# Intelligent_Agriculture_Power.net
KiCad netlist of a schematic drawn in Altium Designer
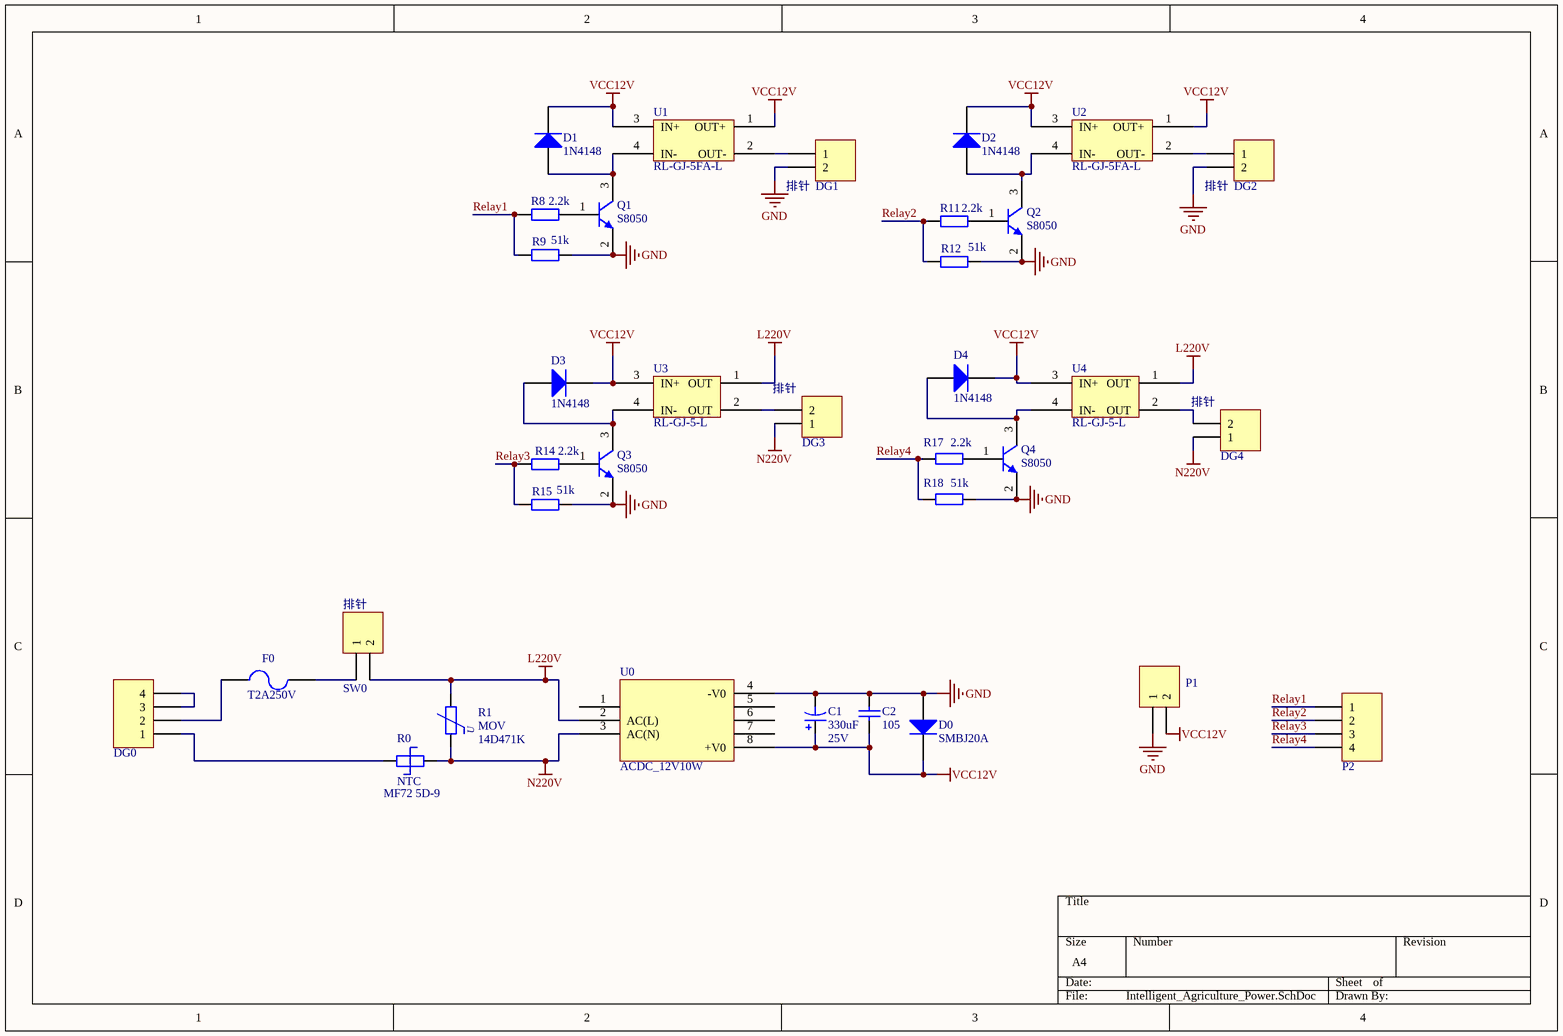
[diagram p0: Intelligent_Agriculture_Power.SchDoc]

(export (version "E")
  (design (tool "Eeschema 10.0.6"))
  (components
    (comp (ref "C1")
      (value "330uF")
      (footprint "C-RB-2.54")
      (description "电解电容")
      (fields
        (field (name "VOL") "25V")
        (field (name "Comment") "Cap Pol1")
        (field (name "PUBLISHER") "Altium Limited")
      )
      (libsource (lib "Miscellaneous Devices") (part "Cap Pol1"))
    )
    (comp (ref "C2")
      (value "105")
      (footprint "C-RAD-0805")
      (description "无极性电容")
      (fields (field (name "Comment") "Cap") (field (name "PUBLISHER") "Altium Limited"))
      (libsource (lib "Intelligent_Agriculture_Lib") (part "Cap"))
    )
    (comp (ref "D0")
      (value "SMBJ20A")
      (footprint "DIODE-1206")
      (description "二极管")
      (fields (field (name "Comment") "Diode") (field (name "PUBLISHER") "Altium Limited"))
      (libsource (lib "Intelligent_Agriculture_Lib") (part "Diode"))
    )
    (comp (ref "D1")
      (value "1N4148")
      (footprint "DIODE-1206")
      (description "二极管")
      (fields (field (name "Comment") "Diode") (field (name "PUBLISHER") "Altium Limited"))
      (libsource (lib "Intelligent_Agriculture_Lib") (part "Diode"))
    )
    (comp (ref "D2")
      (value "1N4148")
      (footprint "DIODE-1206")
      (description "二极管")
      (fields (field (name "Comment") "Diode") (field (name "PUBLISHER") "Altium Limited"))
      (libsource (lib "Intelligent_Agriculture_Lib") (part "Diode"))
    )
    (comp (ref "D3")
      (value "1N4148")
      (footprint "DIODE-1206")
      (description "二极管")
      (fields (field (name "Comment") "Diode") (field (name "PUBLISHER") "Altium Limited"))
      (libsource (lib "Intelligent_Agriculture_Lib") (part "Diode"))
    )
    (comp (ref "D4")
      (value "1N4148")
      (footprint "DIODE-1206")
      (description "二极管")
      (fields (field (name "Comment") "Diode") (field (name "PUBLISHER") "Altium Limited"))
      (libsource (lib "Intelligent_Agriculture_Lib") (part "Diode"))
    )
    (comp (ref "DG0")
      (value "Header 4")
      (footprint "DG301-4P")
      (description "接插件")
      (fields (field (name "PUBLISHER") "Altium Limited"))
      (libsource (lib "Intelligent_Agriculture_Lib") (part "Header 4"))
    )
    (comp (ref "DG1")
      (value "Header 2")
      (footprint "DG301-2P")
      (description "接插件")
      (fields (field (name "PUBLISHER") "Altium Limited"))
      (libsource (lib "Intelligent_Agriculture_Lib") (part "Header 2"))
    )
    (comp (ref "DG2")
      (value "Header 2")
      (footprint "DG301-2P")
      (description "接插件")
      (fields (field (name "PUBLISHER") "Altium Limited"))
      (libsource (lib "Intelligent_Agriculture_Lib") (part "Header 2"))
    )
    (comp (ref "DG3")
      (value "Header 2")
      (footprint "DG301-2P")
      (description "接插件")
      (fields (field (name "PUBLISHER") "Altium Limited"))
      (libsource (lib "") (part "Header 2_1"))
    )
    (comp (ref "DG4")
      (value "Header 2")
      (footprint "DG301-2P")
      (description "接插件")
      (fields (field (name "PUBLISHER") "Altium Limited"))
      (libsource (lib "") (part "Header 2_1"))
    )
    (comp (ref "F0")
      (value "T2A250V")
      (description "保险丝")
      (fields (field (name "Comment") "Fuse") (field (name "PUBLISHER") "Altium Limited"))
      (libsource (lib "fszhang") (part "Fuse 2"))
    )
    (comp (ref "P1")
      (value "Header 2")
      (footprint "HDR2X1_B1")
      (description "接插件")
      (fields (field (name "PUBLISHER") "Altium Limited"))
      (libsource (lib "fszhang") (part "Header 2"))
    )
    (comp (ref "P2")
      (value "Header 4")
      (footprint "HDR4X1_B1")
      (description "接插件")
      (fields (field (name "PUBLISHER") "Altium Limited"))
      (libsource (lib "fszhang") (part "Header 4"))
    )
    (comp (ref "Q1")
      (value "S8050")
      (footprint "SOT-23")
      (description "NPN三极管")
      (fields (field (name "PUBLISHER") "Altium Limited"))
      (libsource (lib "fszhang") (part "BCP68"))
    )
    (comp (ref "Q2")
      (value "S8050")
      (description "NPN三极管")
      (fields (field (name "PUBLISHER") "Altium Limited"))
      (libsource (lib "fszhang") (part "BCP68"))
    )
    (comp (ref "Q3")
      (value "S8050")
      (description "NPN三极管")
      (fields (field (name "PUBLISHER") "Altium Limited"))
      (libsource (lib "fszhang") (part "BCP68"))
    )
    (comp (ref "Q4")
      (value "S8050")
      (description "NPN三极管")
      (fields (field (name "PUBLISHER") "Altium Limited"))
      (libsource (lib "fszhang") (part "BCP68"))
    )
    (comp (ref "R0")
      (value "NTC")
      (description "热敏电阻")
      (fields (field (name "ALTIUM_VALUE") "MF72 5D-9") (field (name "PUBLISHER") "Altium Limited"))
      (libsource (lib "fszhang") (part "NTC"))
    )
    (comp (ref "R1")
      (value "MOV")
      (description "压敏电阻")
      (fields (field (name "ALTIUM_VALUE") "14D471K") (field (name "PUBLISHER") "Altium Limited"))
      (libsource (lib "fszhang") (part "MOV"))
    )
    (comp (ref "R8")
      (value "2.2k")
      (description "贴片电阻")
      (fields (field (name "Comment") "Res1") (field (name "PUBLISHER") "Altium Limited"))
      (libsource (lib "") (part "Res1_1"))
    )
    (comp (ref "R9")
      (value "51k")
      (description "贴片电阻")
      (fields (field (name "Comment") "Res1") (field (name "PUBLISHER") "Altium Limited"))
      (libsource (lib "fszhang") (part "Res1"))
    )
    (comp (ref "R11")
      (value "2.2k")
      (description "贴片电阻")
      (fields (field (name "Comment") "Res1") (field (name "PUBLISHER") "Altium Limited"))
      (libsource (lib "") (part "Res1_1"))
    )
    (comp (ref "R12")
      (value "51k")
      (description "贴片电阻")
      (fields (field (name "Comment") "Res1") (field (name "PUBLISHER") "Altium Limited"))
      (libsource (lib "fszhang") (part "Res1"))
    )
    (comp (ref "R14")
      (value "2.2k")
      (description "贴片电阻")
      (fields (field (name "Comment") "Res1") (field (name "PUBLISHER") "Altium Limited"))
      (libsource (lib "") (part "Res1_1"))
    )
    (comp (ref "R15")
      (value "51k")
      (description "贴片电阻")
      (fields (field (name "Comment") "Res1") (field (name "PUBLISHER") "Altium Limited"))
      (libsource (lib "fszhang") (part "Res1"))
    )
    (comp (ref "R17")
      (value "2.2k")
      (description "贴片电阻")
      (fields (field (name "Comment") "Res1") (field (name "PUBLISHER") "Altium Limited"))
      (libsource (lib "") (part "Res1_1"))
    )
    (comp (ref "R18")
      (value "51k")
      (description "贴片电阻")
      (fields (field (name "Comment") "Res1") (field (name "PUBLISHER") "Altium Limited"))
      (libsource (lib "fszhang") (part "Res1"))
    )
    (comp (ref "SW0")
      (value "Header 2")
      (footprint "DG301-2P")
      (description "接插件")
      (fields (field (name "PUBLISHER") "Altium Limited"))
      (libsource (lib "") (part "Header 2_1"))
    )
    (comp (ref "U0")
      (value "ACDC_12V10W")
      (description "ACDC模块_220VAC转12VDC")
      (libsource (lib "fszhang") (part "ACDC_12V10W"))
    )
    (comp (ref "U1")
      (value "RL-GJ-5FA-L")
      (footprint "RL-GJ-5-L")
      (description "3-38V DC-DC固态继电器")
      (libsource (lib "Intelligent_Agriculture_Lib") (part "RL-GJ-5FA-L"))
    )
    (comp (ref "U2")
      (value "RL-GJ-5FA-L")
      (footprint "RL-GJ-5-L")
      (description "3-38V DC-DC固态继电器")
      (libsource (lib "Intelligent_Agriculture_Lib") (part "RL-GJ-5FA-L"))
    )
    (comp (ref "U3")
      (value "RL-GJ-5-L")
      (footprint "RL-GJ-5-L")
      (description "3-38V DC-AC固态继电器")
      (libsource (lib "Intelligent_Agriculture_Lib") (part "RL-GJ-5-L"))
    )
    (comp (ref "U4")
      (value "RL-GJ-5-L")
      (footprint "RL-GJ-5-L")
      (description "3-38V DC-AC固态继电器")
      (libsource (lib "Intelligent_Agriculture_Lib") (part "RL-GJ-5-L"))
    )
  )
  (nets
    (net (code "1") (name "/Relay1") (class "Default")
      (node (ref "P2") (pin "1") (pinfunction "1_1") (pintype "passive"))
      (node (ref "R8") (pin "2") (pinfunction "2_2") (pintype "passive"))
      (node (ref "R9") (pin "1") (pinfunction "1_1") (pintype "passive"))
    )
    (net (code "2") (name "/Relay2") (class "Default")
      (node (ref "P2") (pin "2") (pinfunction "2_2") (pintype "passive"))
      (node (ref "R11") (pin "2") (pinfunction "2_2") (pintype "passive"))
      (node (ref "R12") (pin "1") (pinfunction "1_1") (pintype "passive"))
    )
    (net (code "3") (name "/Relay3") (class "Default")
      (node (ref "P2") (pin "3") (pinfunction "3_3") (pintype "passive"))
      (node (ref "R14") (pin "2") (pinfunction "2_2") (pintype "passive"))
      (node (ref "R15") (pin "1") (pinfunction "1_1") (pintype "passive"))
    )
    (net (code "4") (name "/Relay4") (class "Default")
      (node (ref "P2") (pin "4") (pinfunction "4_4") (pintype "passive"))
      (node (ref "R17") (pin "2") (pinfunction "2_2") (pintype "passive"))
      (node (ref "R18") (pin "1") (pinfunction "1_1") (pintype "passive"))
    )
    (net (code "5") (name "GND") (class "Default")
      (node (ref "C1") (pin "2") (pinfunction "2_2") (pintype "passive"))
      (node (ref "C2") (pin "2") (pinfunction "2_2") (pintype "passive"))
      (node (ref "D0") (pin "1") (pinfunction "A_1") (pintype "passive"))
      (node (ref "DG1") (pin "2") (pinfunction "2_2") (pintype "passive"))
      (node (ref "DG2") (pin "2") (pinfunction "2_2") (pintype "passive"))
      (node (ref "P1") (pin "1") (pinfunction "1_1") (pintype "passive"))
      (node (ref "Q1") (pin "2") (pinfunction "E_2") (pintype "passive"))
      (node (ref "Q2") (pin "2") (pinfunction "E_2") (pintype "passive"))
      (node (ref "Q3") (pin "2") (pinfunction "E_2") (pintype "passive"))
      (node (ref "Q4") (pin "2") (pinfunction "E_2") (pintype "passive"))
      (node (ref "R12") (pin "2") (pinfunction "2_2") (pintype "passive"))
      (node (ref "R15") (pin "2") (pinfunction "2_2") (pintype "passive"))
      (node (ref "R18") (pin "2") (pinfunction "2_2") (pintype "passive"))
      (node (ref "R9") (pin "2") (pinfunction "2_2") (pintype "passive"))
      (node (ref "U0") (pin "4") (pinfunction "-V0_4") (pintype "passive"))
    )
    (net (code "6") (name "L220V") (class "Default")
      (node (ref "R1") (pin "2") (pinfunction "2_2") (pintype "passive"))
      (node (ref "SW0") (pin "2") (pinfunction "2_2") (pintype "passive"))
      (node (ref "U0") (pin "2") (pinfunction "AC(L)_2") (pintype "passive"))
      (node (ref "U3") (pin "1") (pinfunction "OUT_1") (pintype "passive"))
      (node (ref "U4") (pin "1") (pinfunction "OUT_1") (pintype "passive"))
    )
    (net (code "7") (name "N220V") (class "Default")
      (node (ref "DG3") (pin "1") (pinfunction "1_1") (pintype "passive"))
      (node (ref "DG4") (pin "1") (pinfunction "1_1") (pintype "passive"))
      (node (ref "R0") (pin "2") (pinfunction "2_2") (pintype "passive"))
      (node (ref "R1") (pin "1") (pinfunction "1_1") (pintype "passive"))
      (node (ref "U0") (pin "3") (pinfunction "AC(N)_3") (pintype "passive"))
    )
    (net (code "8") (name "Net-(D1-A)") (class "Default")
      (node (ref "D1") (pin "1") (pinfunction "A_1") (pintype "passive"))
      (node (ref "Q1") (pin "3") (pinfunction "C_3") (pintype "passive"))
      (node (ref "U1") (pin "4") (pinfunction "IN-_4") (pintype "passive"))
    )
    (net (code "9") (name "Net-(D2-A)") (class "Default")
      (node (ref "D2") (pin "1") (pinfunction "A_1") (pintype "passive"))
      (node (ref "Q2") (pin "3") (pinfunction "C_3") (pintype "passive"))
      (node (ref "U2") (pin "4") (pinfunction "IN-_4") (pintype "passive"))
    )
    (net (code "10") (name "Net-(D3-A)") (class "Default")
      (node (ref "D3") (pin "1") (pinfunction "A_1") (pintype "passive"))
      (node (ref "Q3") (pin "3") (pinfunction "C_3") (pintype "passive"))
      (node (ref "U3") (pin "4") (pinfunction "IN-_4") (pintype "passive"))
    )
    (net (code "11") (name "Net-(D4-A)") (class "Default")
      (node (ref "D4") (pin "1") (pinfunction "A_1") (pintype "passive"))
      (node (ref "Q4") (pin "3") (pinfunction "C_3") (pintype "passive"))
      (node (ref "U4") (pin "4") (pinfunction "IN-_4") (pintype "passive"))
    )
    (net (code "12") (name "Net-(DG0-Pad1)") (class "Default")
      (node (ref "DG0") (pin "1") (pinfunction "1_1") (pintype "passive"))
      (node (ref "R0") (pin "1") (pinfunction "1_1") (pintype "passive"))
    )
    (net (code "13") (name "Net-(DG0-Pad2)") (class "Default")
      (node (ref "DG0") (pin "2") (pinfunction "2_2") (pintype "passive"))
      (node (ref "F0") (pin "1") (pinfunction "1_1") (pintype "passive"))
    )
    (net (code "14") (name "Net-(DG0-Pad3)") (class "Default")
      (node (ref "DG0") (pin "3") (pinfunction "3_3") (pintype "passive"))
      (node (ref "DG0") (pin "4") (pinfunction "4_4") (pintype "passive"))
    )
    (net (code "15") (name "Net-(DG3-Pad2)") (class "Default")
      (node (ref "DG3") (pin "2") (pinfunction "2_2") (pintype "passive"))
      (node (ref "U3") (pin "2") (pinfunction "OUT_2") (pintype "passive"))
    )
    (net (code "16") (name "Net-(DG4-Pad2)") (class "Default")
      (node (ref "DG4") (pin "2") (pinfunction "2_2") (pintype "passive"))
      (node (ref "U4") (pin "2") (pinfunction "OUT_2") (pintype "passive"))
    )
    (net (code "17") (name "Net-(F0-Pad2)") (class "Default")
      (node (ref "F0") (pin "2") (pinfunction "2_2") (pintype "passive"))
      (node (ref "SW0") (pin "1") (pinfunction "1_1") (pintype "passive"))
    )
    (net (code "18") (name "Net-(Q1-B)") (class "Default")
      (node (ref "Q1") (pin "1") (pinfunction "B_1") (pintype "passive"))
      (node (ref "R8") (pin "1") (pinfunction "1_1") (pintype "passive"))
    )
    (net (code "19") (name "Net-(Q2-B)") (class "Default")
      (node (ref "Q2") (pin "1") (pinfunction "B_1") (pintype "passive"))
      (node (ref "R11") (pin "1") (pinfunction "1_1") (pintype "passive"))
    )
    (net (code "20") (name "Net-(Q3-B)") (class "Default")
      (node (ref "Q3") (pin "1") (pinfunction "B_1") (pintype "passive"))
      (node (ref "R14") (pin "1") (pinfunction "1_1") (pintype "passive"))
    )
    (net (code "21") (name "Net-(Q4-B)") (class "Default")
      (node (ref "Q4") (pin "1") (pinfunction "B_1") (pintype "passive"))
      (node (ref "R17") (pin "1") (pinfunction "1_1") (pintype "passive"))
    )
    (net (code "22") (name "Net-(U1-OUT-)") (class "Default")
      (node (ref "DG1") (pin "1") (pinfunction "1_1") (pintype "passive"))
      (node (ref "U1") (pin "2") (pinfunction "OUT-_2") (pintype "passive"))
    )
    (net (code "23") (name "Net-(U2-OUT-)") (class "Default")
      (node (ref "DG2") (pin "1") (pinfunction "1_1") (pintype "passive"))
      (node (ref "U2") (pin "2") (pinfunction "OUT-_2") (pintype "passive"))
    )
    (net (code "24") (name "VCC12V") (class "Default")
      (node (ref "C1") (pin "1") (pinfunction "1_1") (pintype "passive"))
      (node (ref "C2") (pin "1") (pinfunction "1_1") (pintype "passive"))
      (node (ref "D0") (pin "2") (pinfunction "K_2") (pintype "passive"))
      (node (ref "D1") (pin "2") (pinfunction "K_2") (pintype "passive"))
      (node (ref "D2") (pin "2") (pinfunction "K_2") (pintype "passive"))
      (node (ref "D3") (pin "2") (pinfunction "K_2") (pintype "passive"))
      (node (ref "D4") (pin "2") (pinfunction "K_2") (pintype "passive"))
      (node (ref "P1") (pin "2") (pinfunction "2_2") (pintype "passive"))
      (node (ref "U0") (pin "8") (pinfunction "+V0_8") (pintype "passive"))
      (node (ref "U1") (pin "1") (pinfunction "OUT+_1") (pintype "passive"))
      (node (ref "U1") (pin "3") (pinfunction "IN+_3") (pintype "passive"))
      (node (ref "U2") (pin "1") (pinfunction "OUT+_1") (pintype "passive"))
      (node (ref "U2") (pin "3") (pinfunction "IN+_3") (pintype "passive"))
      (node (ref "U3") (pin "3") (pinfunction "IN+_3") (pintype "passive"))
      (node (ref "U4") (pin "3") (pinfunction "IN+_3") (pintype "passive"))
    )
    (net (code "25") (name "unconnected-(U0-Pad1)") (class "Default")
      (node (ref "U0") (pin "1") (pintype "passive"))
    )
    (net (code "26") (name "unconnected-(U0-Pad5)") (class "Default")
      (node (ref "U0") (pin "5") (pintype "passive"))
    )
    (net (code "27") (name "unconnected-(U0-Pad6)") (class "Default")
      (node (ref "U0") (pin "6") (pintype "passive"))
    )
    (net (code "28") (name "unconnected-(U0-Pad7)") (class "Default")
      (node (ref "U0") (pin "7") (pintype "passive"))
    )
  )
)
